# HoloCubicPower_211230.net
KiCad netlist of a schematic drawn in Altium Designer
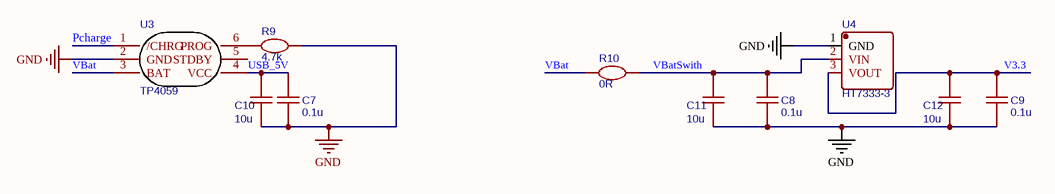
[diagram p0: HoloCubicPower_211230.SchDoc]

(export (version "E")
  (design (tool "Eeschema 10.0.6"))
  (components
    (comp (ref "C7")
      (value "0.1u")
      (footprint "C0603")
      (fields (field (name "CONTRIBUTOR") "LCEDA_Lib"))
      (libsource (lib "altium-import") (part "root_1_0.1u_"))
    )
    (comp (ref "C8")
      (value "0.1u")
      (footprint "C0603")
      (fields (field (name "CONTRIBUTOR") "LCEDA_Lib"))
      (libsource (lib "altium-import") (part "root_1_0.1u_"))
    )
    (comp (ref "C9")
      (value "0.1u")
      (footprint "C0603")
      (fields (field (name "CONTRIBUTOR") "LCEDA_Lib"))
      (libsource (lib "altium-import") (part "root_1_0.1u_"))
    )
    (comp (ref "C10")
      (value "10u")
      (footprint "C0603")
      (fields (field (name "CONTRIBUTOR") "LCEDA_Lib"))
      (libsource (lib "altium-import") (part "root_1_0.1u_"))
    )
    (comp (ref "C11")
      (value "10u")
      (footprint "C0603")
      (fields (field (name "CONTRIBUTOR") "LCEDA_Lib"))
      (libsource (lib "altium-import") (part "root_1_0.1u_"))
    )
    (comp (ref "C12")
      (value "10u")
      (footprint "C0603")
      (fields (field (name "CONTRIBUTOR") "LCEDA_Lib"))
      (libsource (lib "altium-import") (part "root_1_0.1u_"))
    )
    (comp (ref "R9")
      (value "4.7k")
      (footprint "R0603")
      (fields (field (name "CONTRIBUTOR") "LCEDA_Lib"))
      (libsource (lib "altium-import") (part "root_2_10k_"))
    )
    (comp (ref "R10")
      (value "0R")
      (footprint "R0805")
      (fields (field (name "CONTRIBUTOR") "LCEDA_Lib"))
      (libsource (lib "altium-import") (part "root_2_10k_"))
    )
    (comp (ref "U3")
      (value "TP4059")
      (footprint "SOT-23-6")
      (fields (field (name "BOM_SUPPLIER PART") "C80364"))
      (libsource (lib "ZtYADLib") (part "TP4059"))
    )
    (comp (ref "U4")
      (value "HT7333-3")
      (footprint "SOT-89")
      (fields (field (name "BOM_SUPPLIER PART") "C84207"))
      (libsource (lib "ZtYADLib") (part "HT7333-3"))
    )
  )
  (nets
    (net (code "1") (name "/Pcharge") (class "Default")
      (node (ref "U3") (pin "1") (pinfunction "/CHRG_1") (pintype "passive"))
    )
    (net (code "2") (name "/USB_5V") (class "Default")
      (node (ref "C10") (pin "2") (pinfunction "2_2") (pintype "passive"))
      (node (ref "C7") (pin "2") (pinfunction "2_2") (pintype "passive"))
      (node (ref "U3") (pin "4") (pinfunction "VCC_4") (pintype "passive"))
    )
    (net (code "3") (name "/V3.3") (class "Default")
      (node (ref "C12") (pin "2") (pinfunction "2_2") (pintype "passive"))
      (node (ref "C9") (pin "2") (pinfunction "2_2") (pintype "passive"))
      (node (ref "U4") (pin "3") (pinfunction "VOUT_3") (pintype "passive"))
    )
    (net (code "4") (name "/VBat") (class "Default")
      (node (ref "R10") (pin "2") (pinfunction "2_2") (pintype "passive"))
      (node (ref "U3") (pin "3") (pinfunction "BAT_3") (pintype "passive"))
    )
    (net (code "5") (name "/VBatSwith") (class "Default")
      (node (ref "C11") (pin "2") (pinfunction "2_2") (pintype "passive"))
      (node (ref "C8") (pin "2") (pinfunction "2_2") (pintype "passive"))
      (node (ref "R10") (pin "1") (pinfunction "1_1") (pintype "passive"))
      (node (ref "U4") (pin "2") (pinfunction "VIN_2") (pintype "passive"))
    )
    (net (code "6") (name "GND") (class "Default")
      (node (ref "C10") (pin "1") (pinfunction "1_1") (pintype "passive"))
      (node (ref "C11") (pin "1") (pinfunction "1_1") (pintype "passive"))
      (node (ref "C12") (pin "1") (pinfunction "1_1") (pintype "passive"))
      (node (ref "C7") (pin "1") (pinfunction "1_1") (pintype "passive"))
      (node (ref "C8") (pin "1") (pinfunction "1_1") (pintype "passive"))
      (node (ref "C9") (pin "1") (pinfunction "1_1") (pintype "passive"))
      (node (ref "R9") (pin "1") (pinfunction "1_1") (pintype "passive"))
      (node (ref "U3") (pin "2") (pinfunction "GND_2") (pintype "passive"))
      (node (ref "U4") (pin "1") (pinfunction "GND_1") (pintype "passive"))
    )
    (net (code "7") (name "Net-(U3-PROG)") (class "Default")
      (node (ref "R9") (pin "2") (pinfunction "2_2") (pintype "passive"))
      (node (ref "U3") (pin "6") (pinfunction "PROG_6") (pintype "passive"))
    )
    (net (code "8") (name "unconnected-(U3-STDBY-Pad5)") (class "Default")
      (node (ref "U3") (pin "5") (pinfunction "STDBY_5") (pintype "passive"))
    )
  )
)
